# BATTERY_GESTION.net
KiCad netlist of a schematic drawn in Altium Designer
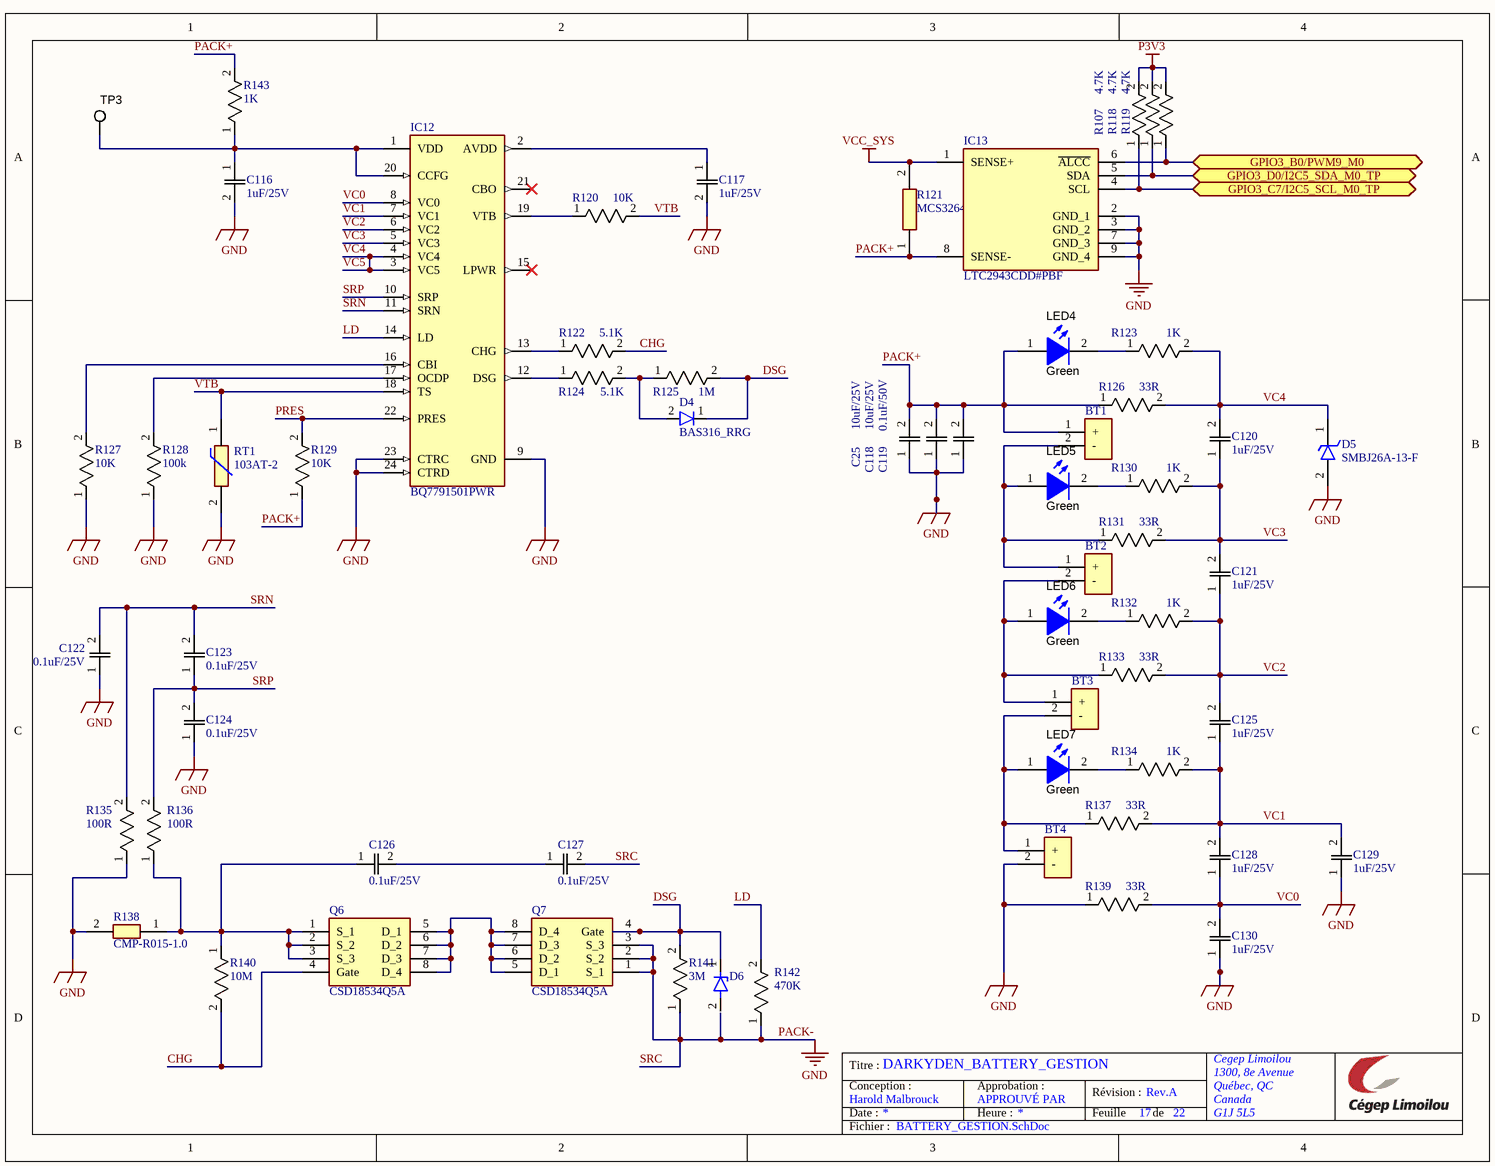
[diagram p0: BATTERY_GESTION.SchDoc]

(export (version "E")
  (design (tool "Eeschema 10.0.6"))
  (components
    (comp (ref "BT1")
      (value "0530480210")
      (footprint "SamacSys:SHDRRA2W35P0X125_1X2_425X550X350P")
      (description "Connector")
      (libsource (lib "SamacSys") (part "Header 1.25MM"))
    )
    (comp (ref "BT2")
      (value "0530480210")
      (footprint "SamacSys:SHDRRA2W35P0X125_1X2_425X550X350P")
      (description "Connector")
      (libsource (lib "SamacSys") (part "Header 1.25MM"))
    )
    (comp (ref "BT3")
      (value "0530480210")
      (footprint "SamacSys:SHDRRA2W35P0X125_1X2_425X550X350P")
      (description "Connector")
      (libsource (lib "SamacSys") (part "Header 1.25MM"))
    )
    (comp (ref "BT4")
      (value "0530480210")
      (footprint "SamacSys:SHDRRA2W35P0X125_1X2_425X550X350P")
      (description "Connector")
      (libsource (lib "SamacSys") (part "Header 1.25MM"))
    )
    (comp (ref "C25")
      (value "10uF/25V")
      (footprint "CAPC220145_88N_KEM")
      (description "10uF / 25 VDC, +85degC, X5R Dielec, +/-10% ¦ KEMET C0805C106K3PACTU 0805")
      (fields
        (field (name "MANUFACTURER") "KEMET")
        (field (name "MANUFACTURER PART NUMBER") "C0805C106K3PACTU")
      )
      (libsource (lib "C0805C106K3PACTU") (part "C0805C106K3PACTU"))
    )
    (comp (ref "C116")
      (value "1uF/25V")
      (footprint "SamacSys:C0805")
      (description "1 µF, 25 V (DC), ±10 %, SMD 0805, X7R, C0805C105K3RAC7800")
      (fields
        (field (name "MANUFACTURER_PART_NUMBER") "C0805C105K3RACTU")
        (field (name "MOUSER PART NUMBER") "80-C0805C105K3R")
      )
      (libsource (lib "SamacSys") (part "C0805C105K3RACTU"))
    )
    (comp (ref "C117")
      (value "1uF/25V")
      (footprint "SamacSys:C0805")
      (description "1 µF, 25 V (DC), ±10 %, SMD 0805, X7R, C0805C105K3RAC7800")
      (fields
        (field (name "MANUFACTURER_PART_NUMBER") "C0805C105K3RACTU")
        (field (name "MOUSER PART NUMBER") "80-C0805C105K3R")
      )
      (libsource (lib "SamacSys") (part "C0805C105K3RACTU"))
    )
    (comp (ref "C118")
      (value "10uF/25V")
      (footprint "CAPC220145_88N_KEM")
      (description "10uF / 25 VDC, +85degC, X5R Dielec, +/-10% ¦ KEMET C0805C106K3PACTU 0805")
      (fields
        (field (name "MANUFACTURER") "KEMET")
        (field (name "MANUFACTURER PART NUMBER") "C0805C106K3PACTU")
      )
      (libsource (lib "C0805C106K3PACTU") (part "C0805C106K3PACTU"))
    )
    (comp (ref "C119")
      (value "0.1uF/50V")
      (footprint "SamacSys:C0805")
      (description "0.1uF/50V X7R 10% 0805 Multilayer Ceramic Capacitors Mlcc Smd/Smt Rohs")
      (fields
        (field (name "MANUFACTURER_PART_NUMBER") "C0805C104K5RACTU")
        (field (name "MOUSER PART NUMBER") "80-C0805C104K5R")
      )
      (libsource (lib "SamacSys") (part "C0805C104K5RACTU"))
    )
    (comp (ref "C120")
      (value "1uF/25V")
      (footprint "SamacSys:C0805")
      (description "1 µF, 25 V (DC), ±10 %, SMD 0805, X7R, C0805C105K3RAC7800")
      (fields
        (field (name "MANUFACTURER_PART_NUMBER") "C0805C105K3RACTU")
        (field (name "MOUSER PART NUMBER") "80-C0805C105K3R")
      )
      (libsource (lib "SamacSys") (part "C0805C105K3RACTU"))
    )
    (comp (ref "C121")
      (value "1uF/25V")
      (footprint "SamacSys:C0805")
      (description "1 µF, 25 V (DC), ±10 %, SMD 0805, X7R, C0805C105K3RAC7800")
      (fields
        (field (name "MANUFACTURER_PART_NUMBER") "C0805C105K3RACTU")
        (field (name "MOUSER PART NUMBER") "80-C0805C105K3R")
      )
      (libsource (lib "SamacSys") (part "C0805C105K3RACTU"))
    )
    (comp (ref "C122")
      (value "0.1uF/25V")
      (footprint "CAPC220145_88N_KEM")
      (description "0.1uF 25V X7R 10% SMD 0805 125C Plastic T/R")
      (fields
        (field (name "MANUFACTURER") "KEMET")
        (field (name "MANUFACTURER PART NUMBER") "C0805C104K3RACTU")
      )
      (libsource (lib "C0805C104K3RACTU") (part "C0805C104K3RACTU"))
    )
    (comp (ref "C123")
      (value "0.1uF/25V")
      (footprint "CAPC220145_88N_KEM")
      (description "0.1uF 25V X7R 10% SMD 0805 125C Plastic T/R")
      (fields
        (field (name "MANUFACTURER") "KEMET")
        (field (name "MANUFACTURER PART NUMBER") "C0805C104K3RACTU")
      )
      (libsource (lib "C0805C104K3RACTU") (part "C0805C104K3RACTU"))
    )
    (comp (ref "C124")
      (value "0.1uF/25V")
      (footprint "CAPC220145_88N_KEM")
      (description "0.1uF 25V X7R 10% SMD 0805 125C Plastic T/R")
      (fields
        (field (name "MANUFACTURER") "KEMET")
        (field (name "MANUFACTURER PART NUMBER") "C0805C104K3RACTU")
      )
      (libsource (lib "C0805C104K3RACTU") (part "C0805C104K3RACTU"))
    )
    (comp (ref "C125")
      (value "1uF/25V")
      (footprint "SamacSys:C0805")
      (description "1 µF, 25 V (DC), ±10 %, SMD 0805, X7R, C0805C105K3RAC7800")
      (fields
        (field (name "MANUFACTURER_PART_NUMBER") "C0805C105K3RACTU")
        (field (name "MOUSER PART NUMBER") "80-C0805C105K3R")
      )
      (libsource (lib "SamacSys") (part "C0805C105K3RACTU"))
    )
    (comp (ref "C126")
      (value "0.1uF/25V")
      (footprint "CAPC220145_88N_KEM")
      (description "0.1uF 25V X7R 10% SMD 0805 125C Plastic T/R")
      (fields
        (field (name "MANUFACTURER") "KEMET")
        (field (name "MANUFACTURER PART NUMBER") "C0805C104K3RACTU")
      )
      (libsource (lib "C0805C104K3RACTU") (part "C0805C104K3RACTU"))
    )
    (comp (ref "C127")
      (value "0.1uF/25V")
      (footprint "CAPC220145_88N_KEM")
      (description "0.1uF 25V X7R 10% SMD 0805 125C Plastic T/R")
      (fields
        (field (name "MANUFACTURER") "KEMET")
        (field (name "MANUFACTURER PART NUMBER") "C0805C104K3RACTU")
      )
      (libsource (lib "C0805C104K3RACTU") (part "C0805C104K3RACTU"))
    )
    (comp (ref "C128")
      (value "1uF/25V")
      (footprint "SamacSys:C0805")
      (description "1 µF, 25 V (DC), ±10 %, SMD 0805, X7R, C0805C105K3RAC7800")
      (fields
        (field (name "MANUFACTURER_PART_NUMBER") "C0805C105K3RACTU")
        (field (name "MOUSER PART NUMBER") "80-C0805C105K3R")
      )
      (libsource (lib "SamacSys") (part "C0805C105K3RACTU"))
    )
    (comp (ref "C129")
      (value "1uF/25V")
      (footprint "SamacSys:C0805")
      (description "1 µF, 25 V (DC), ±10 %, SMD 0805, X7R, C0805C105K3RAC7800")
      (fields
        (field (name "MANUFACTURER_PART_NUMBER") "C0805C105K3RACTU")
        (field (name "MOUSER PART NUMBER") "80-C0805C105K3R")
      )
      (libsource (lib "SamacSys") (part "C0805C105K3RACTU"))
    )
    (comp (ref "C130")
      (value "1uF/25V")
      (footprint "SamacSys:C0805")
      (description "1 µF, 25 V (DC), ±10 %, SMD 0805, X7R, C0805C105K3RAC7800")
      (fields
        (field (name "MANUFACTURER_PART_NUMBER") "C0805C105K3RACTU")
        (field (name "MOUSER PART NUMBER") "80-C0805C105K3R")
      )
      (libsource (lib "SamacSys") (part "C0805C105K3RACTU"))
    )
    (comp (ref "D4")
      (value "BAS316_RRG")
      (footprint "SamacSys:BAS316RRG")
      (description "Rectifier Diode Small Signal Switching 0.25A 4ns 2-Pin SOD-323 T/R")
      (fields
        (field (name "MANUFACTURER_PART_NUMBER") "BAS316 RRG")
        (field (name "MOUSER PART NUMBER") "821-BAS316RRG")
      )
      (libsource (lib "SamacSys") (part "BAS316_RRG"))
    )
    (comp (ref "D5")
      (value "SMBJ26A-13-F")
      (footprint "SamacSys:DIOM5336X250N")
      (description "TVS DIODE 26VWM 42.1VC SMB")
      (fields (field (name "MOUSER PART NUMBER") "621-SMBJ26A-13-F"))
      (libsource (lib "SamacSys") (part "SMBJ26A-13-F"))
    )
    (comp (ref "D6")
      (value "MMSZ5248B-7-F")
      (footprint "SamacSys:SOD3716X115N")
      (description "Zener Diode 18 V 500 mW ±5% Surface Mount SOD-123")
      (libsource (lib "SamacSys") (part "MMSZ5248B-7-F"))
    )
    (comp (ref "IC12")
      (value "BQ7791501PWR")
      (footprint "SamacSys:SOP65P640X120-24N")
      (description "/Polymer 3~5 TSSOP-24 Battery Management ICs ROHS")
      (fields
        (field (name "MOUSER PART NUMBER") "595-BQ7791501PWR")
        (field (name "MANUFACTURER") "Texas Instruments")
      )
      (libsource (lib "SamacSys") (part "BQ7791501PWR"))
    )
    (comp (ref "IC13")
      (value "LTC2943CDD#PBF")
      (footprint "SamacSys:SON50P300X300X80-9N-D")
      (description "LTC2943 - Multicell Battery Gas Gauge with Temperature, Voltage and Current Measurement")
      (fields
        (field (name "MOUSER PART NUMBER") "584-LTC2943CDD#PBF")
        (field (name "MANUFACTURER") "Analog Devices / Linear Technology")
      )
      (libsource (lib "SamacSys") (part "LTC2943CDD#PBF"))
    )
    (comp (ref "LED4")
      (value "Green")
      (footprint "LED_LTST-C190")
      (description "LED, Green, SMD")
      (fields (field (name "MANUFACTURER") "Lite-On") (field (name "PARTNUMBER") "LTST-C190GKT"))
      (libsource (lib "texas_instrument_power") (part "LED_Gr_SMD"))
    )
    (comp (ref "LED5")
      (value "Green")
      (footprint "LED_LTST-C190")
      (description "LED, Green, SMD")
      (fields (field (name "MANUFACTURER") "Lite-On") (field (name "PARTNUMBER") "LTST-C190GKT"))
      (libsource (lib "texas_instrument_power") (part "LED_Gr_SMD"))
    )
    (comp (ref "LED6")
      (value "Green")
      (footprint "LED_LTST-C190")
      (description "LED, Green, SMD")
      (fields (field (name "MANUFACTURER") "Lite-On") (field (name "PARTNUMBER") "LTST-C190GKT"))
      (libsource (lib "texas_instrument_power") (part "LED_Gr_SMD"))
    )
    (comp (ref "LED7")
      (value "Green")
      (footprint "LED_LTST-C190")
      (description "LED, Green, SMD")
      (fields (field (name "MANUFACTURER") "Lite-On") (field (name "PARTNUMBER") "LTST-C190GKT"))
      (libsource (lib "texas_instrument_power") (part "LED_Gr_SMD"))
    )
    (comp (ref "Q6")
      (value "CSD18534Q5A")
      (footprint "SamacSys:Q5A")
      (description "MOSFET N-Channel 60 V 13A (Ta), 50A (Tc) 3.1W (Ta), 77W (Tc) Surface Mount 8-VSONP (5x6)")
      (fields (field (name "MOUSER PART NUMBER") "595-CSD18534Q5A"))
      (libsource (lib "") (part "CSD18534Q5A_1"))
    )
    (comp (ref "Q7")
      (value "CSD18534Q5A")
      (footprint "SamacSys:Q5A")
      (description "MOSFET N-Channel 60 V 13A (Ta), 50A (Tc) 3.1W (Ta), 77W (Tc) Surface Mount 8-VSONP (5x6)")
      (fields (field (name "MOUSER PART NUMBER") "595-CSD18534Q5A"))
      (libsource (lib "SamacSys") (part "CSD18534Q5A"))
    )
    (comp (ref "R107")
      (value "4.7K")
      (footprint "RC0603N_PAN")
      (description "Res Thin Film 0603 4.7K Ohm 0.1% 0.1W ±25ppm/°C Molded SMD Punched Carrier T/R")
      (fields
        (field (name "MANUFACTURER") "Panasonic")
        (field (name "MANUFACTURER PART NUMBER") "ERA-3AEB472V")
      )
      (libsource (lib "ERA-3AEB472V") (part "ERA-3AEB472V"))
    )
    (comp (ref "R118")
      (value "4.7K")
      (footprint "RC0603N_PAN")
      (description "Res Thin Film 0603 4.7K Ohm 0.1% 0.1W ±25ppm/°C Molded SMD Punched Carrier T/R")
      (fields
        (field (name "MANUFACTURER") "Panasonic")
        (field (name "MANUFACTURER PART NUMBER") "ERA-3AEB472V")
      )
      (libsource (lib "ERA-3AEB472V") (part "ERA-3AEB472V"))
    )
    (comp (ref "R119")
      (value "4.7K")
      (footprint "RC0603N_PAN")
      (description "Res Thin Film 0603 4.7K Ohm 0.1% 0.1W ±25ppm/°C Molded SMD Punched Carrier T/R")
      (fields
        (field (name "MANUFACTURER") "Panasonic")
        (field (name "MANUFACTURER PART NUMBER") "ERA-3AEB472V")
      )
      (libsource (lib "ERA-3AEB472V") (part "ERA-3AEB472V"))
    )
    (comp (ref "R120")
      (value "10K")
      (footprint "SamacSys:ERJ3EKF1000V")
      (description "10K Ohm 5% Res Thick Film 0603  0.1W(1/10W) ±200ppm/C Pad SMD Automotive T/R")
      (fields
        (field (name "MANUFACTURER_PART_NUMBER") "ERJ-3GEYJ103V")
        (field (name "MOUSER PART NUMBER") "667-ERJ-3GEYJ103V")
      )
      (libsource (lib "SamacSys") (part "ERJ-3GEYJ103V"))
    )
    (comp (ref "R121")
      (value "MCS3264R010FER")
      (footprint "SamacSys:RESC6432X62N")
      (description "Res Metal Alloy 2512 0.01 Ohm 1% 2W 50ppm/ C Molded SMD T/R")
      (fields (field (name "MOUSER PART NUMBER") "588-MCS3264R010FER") (field (name "MANUFACTURER") "Ohmite"))
      (libsource (lib "SamacSys") (part "MCS3264R010FER"))
    )
    (comp (ref "R122")
      (value "5.1K")
      (footprint "SamacSys:ERA3AEB101V")
      (description "5.1K Ohm 0.05% 0.1W ±10ppm/°C Molded Res Thin Film 0603 SMD Punched Carrier T/R")
      (fields
        (field (name "MANUFACTURER_PART_NUMBER") "ERA-3ARW512V")
        (field (name "MOUSER PART NUMBER") "667-ERA-3ARW512V")
      )
      (libsource (lib "SamacSys") (part "ERA-3ARW512V"))
    )
    (comp (ref "R123")
      (value "1K")
      (footprint "SamacSys:RESC1608X55N")
      (description "1K Ohm 1% 1/10W Res Thick Film 0603 ±100ppm/°C Molded SMD Punched Carrier T/R")
      (fields
        (field (name "MANUFACTURER_PART_NUMBER") "ERJ-3EKF1001V")
        (field (name "MOUSER PART NUMBER") "667-ERJ-3EKF1001V")
      )
      (libsource (lib "SamacSys") (part "ERJ-3EKF1001V"))
    )
    (comp (ref "R124")
      (value "5.1K")
      (footprint "SamacSys:ERA3AEB101V")
      (description "5.1K Ohm 0.05% 0.1W ±10ppm/°C Molded Res Thin Film 0603 SMD Punched Carrier T/R")
      (fields
        (field (name "MANUFACTURER_PART_NUMBER") "ERA-3ARW512V")
        (field (name "MOUSER PART NUMBER") "667-ERA-3ARW512V")
      )
      (libsource (lib "SamacSys") (part "ERA-3ARW512V"))
    )
    (comp (ref "R125")
      (value "1M")
      (footprint "SamacSys:ERJ3EKF1000V")
      (description "1M Ohm Res Thick Film 0603 5% 0.1W(1/10W) +/-200ppm/ßC SMD Automotive T/R")
      (fields
        (field (name "MANUFACTURER_PART_NUMBER") "ERJ-3GEYJ105V")
        (field (name "MOUSER PART NUMBER") "667-ERJ-3GEYJ105V")
      )
      (libsource (lib "SamacSys") (part "ERJ-3GEYJ105V"))
    )
    (comp (ref "R126")
      (value "33R")
      (footprint "RC0603N_PAN")
      (description "Res Thick Film 0603 33 Ohm 1% 0.1W ±100ppm/°C Molded SMD Punched Carrier T/R")
      (fields
        (field (name "MANUFACTURER") "Panasonic")
        (field (name "MANUFACTURER PART NUMBER") "ERJ-3EKF33R0V")
      )
      (libsource (lib "ERJ-3EKF33R0V") (part "ERJ-3EKF33R0V"))
    )
    (comp (ref "R127")
      (value "10K")
      (footprint "SamacSys:ERJ3EKF1000V")
      (description "10K Ohm 5% Res Thick Film 0603  0.1W(1/10W) ±200ppm/C Pad SMD Automotive T/R")
      (fields
        (field (name "MANUFACTURER_PART_NUMBER") "ERJ-3GEYJ103V")
        (field (name "MOUSER PART NUMBER") "667-ERJ-3GEYJ103V")
      )
      (libsource (lib "SamacSys") (part "ERJ-3GEYJ103V"))
    )
    (comp (ref "R128")
      (value "100k")
      (footprint "SamacSys:ERJ3EKF1000V")
      (description "100K Ohm 5%  Res Thick Film 0603 1/10W +/-200ppm/ßC Molded SMD Punched Carrier T/R")
      (fields
        (field (name "MANUFACTURER_PART_NUMBER") "ERJ-3GEYJ104V")
        (field (name "MOUSER PART NUMBER") "667-ERJ-3GEYJ104V")
      )
      (libsource (lib "SamacSys") (part "ERJ-3GEYJ104V"))
    )
    (comp (ref "R129")
      (value "10K")
      (footprint "SamacSys:ERJ3EKF1000V")
      (description "10K Ohm 5% Res Thick Film 0603  0.1W(1/10W) ±200ppm/C Pad SMD Automotive T/R")
      (fields
        (field (name "MANUFACTURER_PART_NUMBER") "ERJ-3GEYJ103V")
        (field (name "MOUSER PART NUMBER") "667-ERJ-3GEYJ103V")
      )
      (libsource (lib "SamacSys") (part "ERJ-3GEYJ103V"))
    )
    (comp (ref "R130")
      (value "1K")
      (footprint "SamacSys:RESC1608X55N")
      (description "1K Ohm 1% 1/10W Res Thick Film 0603 ±100ppm/°C Molded SMD Punched Carrier T/R")
      (fields
        (field (name "MANUFACTURER_PART_NUMBER") "ERJ-3EKF1001V")
        (field (name "MOUSER PART NUMBER") "667-ERJ-3EKF1001V")
      )
      (libsource (lib "SamacSys") (part "ERJ-3EKF1001V"))
    )
    (comp (ref "R131")
      (value "33R")
      (footprint "RC0603N_PAN")
      (description "Res Thick Film 0603 33 Ohm 1% 0.1W ±100ppm/°C Molded SMD Punched Carrier T/R")
      (fields
        (field (name "MANUFACTURER") "Panasonic")
        (field (name "MANUFACTURER PART NUMBER") "ERJ-3EKF33R0V")
      )
      (libsource (lib "ERJ-3EKF33R0V") (part "ERJ-3EKF33R0V"))
    )
    (comp (ref "R132")
      (value "1K")
      (footprint "SamacSys:RESC1608X55N")
      (description "1K Ohm 1% 1/10W Res Thick Film 0603 ±100ppm/°C Molded SMD Punched Carrier T/R")
      (fields
        (field (name "MANUFACTURER_PART_NUMBER") "ERJ-3EKF1001V")
        (field (name "MOUSER PART NUMBER") "667-ERJ-3EKF1001V")
      )
      (libsource (lib "SamacSys") (part "ERJ-3EKF1001V"))
    )
    (comp (ref "R133")
      (value "33R")
      (footprint "RC0603N_PAN")
      (description "Res Thick Film 0603 33 Ohm 1% 0.1W ±100ppm/°C Molded SMD Punched Carrier T/R")
      (fields
        (field (name "MANUFACTURER") "Panasonic")
        (field (name "MANUFACTURER PART NUMBER") "ERJ-3EKF33R0V")
      )
      (libsource (lib "ERJ-3EKF33R0V") (part "ERJ-3EKF33R0V"))
    )
    (comp (ref "R134")
      (value "1K")
      (footprint "SamacSys:RESC1608X55N")
      (description "1K Ohm 1% 1/10W Res Thick Film 0603 ±100ppm/°C Molded SMD Punched Carrier T/R")
      (fields
        (field (name "MANUFACTURER_PART_NUMBER") "ERJ-3EKF1001V")
        (field (name "MOUSER PART NUMBER") "667-ERJ-3EKF1001V")
      )
      (libsource (lib "SamacSys") (part "ERJ-3EKF1001V"))
    )
    (comp (ref "R135")
      (value "100R")
      (footprint "SamacSys:RESC1608X55N")
      (description "100 Ohm 1% 1/10W 0603 ±100ppm/°C Molded SMD Punched Carrier T/R")
      (fields
        (field (name "MANUFACTURER_PART_NUMBER") "ERJ-3EKF1000V")
        (field (name "MOUSER PART NUMBER") "667-ERJ-3EKF1000V")
      )
      (libsource (lib "SamacSys") (part "ERJ-3EKF1000V"))
    )
    (comp (ref "R136")
      (value "100R")
      (footprint "SamacSys:RESC1608X55N")
      (description "100 Ohm 1% 1/10W 0603 ±100ppm/°C Molded SMD Punched Carrier T/R")
      (fields
        (field (name "MANUFACTURER_PART_NUMBER") "ERJ-3EKF1000V")
        (field (name "MOUSER PART NUMBER") "667-ERJ-3EKF1000V")
      )
      (libsource (lib "SamacSys") (part "ERJ-3EKF1000V"))
    )
    (comp (ref "R137")
      (value "33R")
      (footprint "RC0603N_PAN")
      (description "Res Thick Film 0603 33 Ohm 1% 0.1W ±100ppm/°C Molded SMD Punched Carrier T/R")
      (fields
        (field (name "MANUFACTURER") "Panasonic")
        (field (name "MANUFACTURER PART NUMBER") "ERJ-3EKF33R0V")
      )
      (libsource (lib "ERJ-3EKF33R0V") (part "ERJ-3EKF33R0V"))
    )
    (comp (ref "R138")
      (value "CMP-R015-1.0")
      (footprint "SamacSys:RESC5025X70N")
      (description "Package 2010")
      (fields
        (field (name "MANUFACTURER_PART_NUMBER") "CRCW20100000Z0EFHP")
        (field (name "MOUSER PART NUMBER") "71-CRCW20100000Z0EFH")
      )
      (libsource (lib "SamacSys") (part "Resistor 2010"))
    )
    (comp (ref "R139")
      (value "33R")
      (footprint "RC0603N_PAN")
      (description "Res Thick Film 0603 33 Ohm 1% 0.1W ±100ppm/°C Molded SMD Punched Carrier T/R")
      (fields
        (field (name "MANUFACTURER") "Panasonic")
        (field (name "MANUFACTURER PART NUMBER") "ERJ-3EKF33R0V")
      )
      (libsource (lib "ERJ-3EKF33R0V") (part "ERJ-3EKF33R0V"))
    )
    (comp (ref "R140")
      (value "10M")
      (footprint "SamacSys:ERJS03J155V")
      (description "10Mohm 5%  SMD 0603   Anti-Sulfur AEC-Q200")
      (fields
        (field (name "MANUFACTURER_PART_NUMBER") "ERJ-U03J106V")
        (field (name "MOUSER PART NUMBER") "667-ERJ-U03J106V")
      )
      (libsource (lib "SamacSys") (part "ERJ-U03J106V"))
    )
    (comp (ref "R141")
      (value "3M")
      (footprint "SamacSys:ERJ3EKF1000V")
      (description "3M Ohm 5% 1/10W Res Thick Film 0603 -400ppm/ to 150p¦")
      (fields
        (field (name "MANUFACTURER_PART_NUMBER") "ERJ-3GEYJ305V")
        (field (name "MOUSER PART NUMBER") "667-ERJ-3GEYJ305V")
      )
      (libsource (lib "SamacSys") (part "ERJ-3GEYJ305V"))
    )
    (comp (ref "R142")
      (value "470K")
      (footprint "SamacSys:RESC1608X55N")
      (description "470K Ohm 1% 0.1W  Res Thick Film 0603 ±100ppm/°C Molded SMD Punched Carrier T/R")
      (fields
        (field (name "MANUFACTURER_PART_NUMBER") "ERJ-3EKF4703V")
        (field (name "MOUSER PART NUMBER") "667-ERJ-3EKF4703V")
      )
      (libsource (lib "SamacSys") (part "ERJ-3EKF4703V"))
    )
    (comp (ref "R143")
      (value "1K")
      (footprint "SamacSys:RESC1608X55N")
      (description "1K Ohm 1% 1/10W Res Thick Film 0603 ±100ppm/°C Molded SMD Punched Carrier T/R")
      (fields
        (field (name "MANUFACTURER_PART_NUMBER") "ERJ-3EKF1001V")
        (field (name "MOUSER PART NUMBER") "667-ERJ-3EKF1001V")
      )
      (libsource (lib "SamacSys") (part "ERJ-3EKF1001V"))
    )
    (comp (ref "RT1")
      (value "103AT-2")
      (footprint "SamacSys:103AT2")
      (description "NTC Thermistor 10k Bead")
      (fields (field (name "MOUSER PART NUMBER") "954-103AT-2"))
      (libsource (lib "SamacSys") (part "103AT-2"))
    )
    (comp (ref "TP3")
      (value "5016")
      (footprint "Testpoint_Keystone_Compact")
      (description "Test Point, Compact, SMT")
      (fields (field (name "MANUFACTURER") "Keystone") (field (name "PUBLISHER") "Texas Instruments"))
      (libsource (lib "texas_instrument_power") (part "TEST_POINT1"))
    )
  )
  (nets
    (net (code "1") (name "/CHG") (class "Default")
      (node (ref "Q6") (pin "4") (pinfunction "Gate_4") (pintype "passive"))
      (node (ref "R122") (pin "2") (pinfunction "2_2") (pintype "passive"))
      (node (ref "R140") (pin "2") (pinfunction "2_2") (pintype "passive"))
    )
    (net (code "2") (name "/DSG") (class "Default")
      (node (ref "D4") (pin "1") (pinfunction "K_1") (pintype "passive"))
      (node (ref "D6") (pin "1") (pinfunction "K_1") (pintype "passive"))
      (node (ref "Q7") (pin "4") (pinfunction "Gate_4") (pintype "passive"))
      (node (ref "R125") (pin "2") (pinfunction "2_2") (pintype "passive"))
      (node (ref "R141") (pin "2") (pinfunction "2_2") (pintype "passive"))
    )
    (net (code "3") (name "/GPIO3_B0{slash}PWM9_M0") (class "Default")
      (node (ref "IC13") (pin "6") (pinfunction "~{ALCC}_6") (pintype "passive"))
      (node (ref "R119") (pin "1") (pinfunction "1_1") (pintype "passive"))
    )
    (net (code "4") (name "/GPIO3_C7{slash}I2C5_SCL_M0_TP") (class "Default")
      (node (ref "IC13") (pin "4") (pinfunction "SCL_4") (pintype "passive"))
      (node (ref "R107") (pin "1") (pinfunction "1_1") (pintype "passive"))
    )
    (net (code "5") (name "/GPIO3_D0{slash}I2C5_SDA_M0_TP") (class "Default")
      (node (ref "IC13") (pin "5") (pinfunction "SDA_5") (pintype "passive"))
      (node (ref "R118") (pin "1") (pinfunction "1_1") (pintype "passive"))
    )
    (net (code "6") (name "/LD") (class "Default")
      (node (ref "IC12") (pin "14") (pinfunction "LD_14") (pintype "input"))
      (node (ref "R142") (pin "2") (pinfunction "2_2") (pintype "passive"))
    )
    (net (code "7") (name "/PACK+") (class "Default")
      (node (ref "BT1") (pin "1") (pinfunction "+_1") (pintype "passive"))
      (node (ref "C118") (pin "2") (pinfunction "2_2") (pintype "passive"))
      (node (ref "C119") (pin "2") (pinfunction "2_2") (pintype "passive"))
      (node (ref "C25") (pin "2") (pinfunction "2_2") (pintype "passive"))
      (node (ref "IC13") (pin "8") (pinfunction "SENSE-_8") (pintype "passive"))
      (node (ref "LED4") (pin "1") (pinfunction "A_1") (pintype "passive"))
      (node (ref "R121") (pin "1") (pinfunction "1_1") (pintype "passive"))
      (node (ref "R126") (pin "1") (pinfunction "1_1") (pintype "passive"))
      (node (ref "R129") (pin "1") (pinfunction "1_1") (pintype "passive"))
      (node (ref "R143") (pin "2") (pinfunction "2_2") (pintype "passive"))
    )
    (net (code "8") (name "/PRES") (class "Default")
      (node (ref "IC12") (pin "22") (pinfunction "PRES_22") (pintype "input"))
      (node (ref "R129") (pin "2") (pinfunction "2_2") (pintype "passive"))
    )
    (net (code "9") (name "/SRN") (class "Default")
      (node (ref "C122") (pin "2") (pinfunction "2_2") (pintype "passive"))
      (node (ref "C123") (pin "2") (pinfunction "2_2") (pintype "passive"))
      (node (ref "IC12") (pin "11") (pinfunction "SRN_11") (pintype "input"))
      (node (ref "R135") (pin "2") (pinfunction "2_2") (pintype "passive"))
    )
    (net (code "10") (name "/SRP") (class "Default")
      (node (ref "C123") (pin "1") (pinfunction "1_1") (pintype "passive"))
      (node (ref "C124") (pin "2") (pinfunction "2_2") (pintype "passive"))
      (node (ref "IC12") (pin "10") (pinfunction "SRP_10") (pintype "input"))
      (node (ref "R136") (pin "2") (pinfunction "2_2") (pintype "passive"))
    )
    (net (code "11") (name "/VC0") (class "Default")
      (node (ref "C128") (pin "1") (pinfunction "1_1") (pintype "passive"))
      (node (ref "C130") (pin "2") (pinfunction "2_2") (pintype "passive"))
      (node (ref "IC12") (pin "8") (pinfunction "VC0_8") (pintype "input"))
      (node (ref "R139") (pin "2") (pinfunction "2_2") (pintype "passive"))
    )
    (net (code "12") (name "/VC1") (class "Default")
      (node (ref "C125") (pin "1") (pinfunction "1_1") (pintype "passive"))
      (node (ref "C128") (pin "2") (pinfunction "2_2") (pintype "passive"))
      (node (ref "C129") (pin "2") (pinfunction "2_2") (pintype "passive"))
      (node (ref "IC12") (pin "7") (pinfunction "VC1_7") (pintype "input"))
      (node (ref "R134") (pin "2") (pinfunction "2_2") (pintype "passive"))
      (node (ref "R137") (pin "2") (pinfunction "2_2") (pintype "passive"))
    )
    (net (code "13") (name "/VC2") (class "Default")
      (node (ref "C121") (pin "1") (pinfunction "1_1") (pintype "passive"))
      (node (ref "C125") (pin "2") (pinfunction "2_2") (pintype "passive"))
      (node (ref "IC12") (pin "6") (pinfunction "VC2_6") (pintype "input"))
      (node (ref "R132") (pin "2") (pinfunction "2_2") (pintype "passive"))
      (node (ref "R133") (pin "2") (pinfunction "2_2") (pintype "passive"))
    )
    (net (code "14") (name "/VC3") (class "Default")
      (node (ref "C120") (pin "1") (pinfunction "1_1") (pintype "passive"))
      (node (ref "C121") (pin "2") (pinfunction "2_2") (pintype "passive"))
      (node (ref "IC12") (pin "5") (pinfunction "VC3_5") (pintype "input"))
      (node (ref "R130") (pin "2") (pinfunction "2_2") (pintype "passive"))
      (node (ref "R131") (pin "2") (pinfunction "2_2") (pintype "passive"))
    )
    (net (code "15") (name "/VC4") (class "Default")
      (node (ref "C120") (pin "2") (pinfunction "2_2") (pintype "passive"))
      (node (ref "D5") (pin "1") (pinfunction "K_1") (pintype "passive"))
      (node (ref "IC12") (pin "3") (pinfunction "VC5_3") (pintype "input"))
      (node (ref "IC12") (pin "4") (pinfunction "VC4_4") (pintype "input"))
      (node (ref "R123") (pin "2") (pinfunction "2_2") (pintype "passive"))
      (node (ref "R126") (pin "2") (pinfunction "2_2") (pintype "passive"))
    )
    (net (code "16") (name "/VTB") (class "Default")
      (node (ref "IC12") (pin "18") (pinfunction "TS_18") (pintype "input"))
      (node (ref "R120") (pin "2") (pinfunction "2_2") (pintype "passive"))
      (node (ref "RT1") (pin "1") (pinfunction "1_1") (pintype "passive"))
    )
    (net (code "17") (name "GND") (class "Default")
      (node (ref "BT4") (pin "2") (pinfunction "-_2") (pintype "passive"))
      (node (ref "C116") (pin "2") (pinfunction "2_2") (pintype "passive"))
      (node (ref "C117") (pin "2") (pinfunction "2_2") (pintype "passive"))
      (node (ref "C118") (pin "1") (pinfunction "1_1") (pintype "passive"))
      (node (ref "C119") (pin "1") (pinfunction "1_1") (pintype "passive"))
      (node (ref "C122") (pin "1") (pinfunction "1_1") (pintype "passive"))
      (node (ref "C124") (pin "1") (pinfunction "1_1") (pintype "passive"))
      (node (ref "C127") (pin "2") (pinfunction "2_2") (pintype "passive"))
      (node (ref "C129") (pin "1") (pinfunction "1_1") (pintype "passive"))
      (node (ref "C130") (pin "1") (pinfunction "1_1") (pintype "passive"))
      (node (ref "C25") (pin "1") (pinfunction "1_1") (pintype "passive"))
      (node (ref "D5") (pin "2") (pinfunction "A_2") (pintype "passive"))
      (node (ref "IC12") (pin "23") (pinfunction "CTRC_23") (pintype "input"))
      (node (ref "IC12") (pin "24") (pinfunction "CTRD_24") (pintype "input"))
      (node (ref "IC12") (pin "9") (pinfunction "GND_9") (pintype "passive"))
      (node (ref "IC13") (pin "2") (pinfunction "GND_1_2") (pintype "passive"))
      (node (ref "IC13") (pin "3") (pinfunction "GND_2_3") (pintype "passive"))
      (node (ref "IC13") (pin "7") (pinfunction "GND_3_7") (pintype "passive"))
      (node (ref "IC13") (pin "9") (pinfunction "GND_4_9") (pintype "passive"))
      (node (ref "Q7") (pin "1") (pinfunction "S_1_1") (pintype "passive"))
      (node (ref "Q7") (pin "2") (pinfunction "S_2_2") (pintype "passive"))
      (node (ref "Q7") (pin "3") (pinfunction "S_3_3") (pintype "passive"))
      (node (ref "R127") (pin "1") (pinfunction "1_1") (pintype "passive"))
      (node (ref "R128") (pin "1") (pinfunction "1_1") (pintype "passive"))
      (node (ref "R135") (pin "1") (pinfunction "1_1") (pintype "passive"))
      (node (ref "R138") (pin "2") (pinfunction "2_2") (pintype "passive"))
      (node (ref "R139") (pin "1") (pinfunction "1_1") (pintype "passive"))
      (node (ref "R141") (pin "1") (pinfunction "1_1") (pintype "passive"))
      (node (ref "R142") (pin "1") (pinfunction "1_1") (pintype "passive"))
      (node (ref "RT1") (pin "2") (pinfunction "2_2") (pintype "passive"))
    )
    (net (code "18") (name "Net-(BT1--)") (class "Default")
      (node (ref "BT1") (pin "2") (pinfunction "-_2") (pintype "passive"))
      (node (ref "BT2") (pin "1") (pinfunction "+_1") (pintype "passive"))
      (node (ref "LED5") (pin "1") (pinfunction "A_1") (pintype "passive"))
      (node (ref "R131") (pin "1") (pinfunction "1_1") (pintype "passive"))
    )
    (net (code "19") (name "Net-(BT2--)") (class "Default")
      (node (ref "BT2") (pin "2") (pinfunction "-_2") (pintype "passive"))
      (node (ref "BT3") (pin "1") (pinfunction "+_1") (pintype "passive"))
      (node (ref "LED6") (pin "1") (pinfunction "A_1") (pintype "passive"))
      (node (ref "R133") (pin "1") (pinfunction "1_1") (pintype "passive"))
    )
    (net (code "20") (name "Net-(BT3--)") (class "Default")
      (node (ref "BT3") (pin "2") (pinfunction "-_2") (pintype "passive"))
      (node (ref "BT4") (pin "1") (pinfunction "+_1") (pintype "passive"))
      (node (ref "LED7") (pin "1") (pinfunction "A_1") (pintype "passive"))
      (node (ref "R137") (pin "1") (pinfunction "1_1") (pintype "passive"))
    )
    (net (code "21") (name "Net-(C126-Pad2)") (class "Default")
      (node (ref "C126") (pin "2") (pinfunction "2_2") (pintype "passive"))
      (node (ref "C127") (pin "1") (pinfunction "1_1") (pintype "passive"))
    )
    (net (code "22") (name "Net-(D4-A)") (class "Default")
      (node (ref "D4") (pin "2") (pinfunction "A_2") (pintype "passive"))
      (node (ref "R124") (pin "2") (pinfunction "2_2") (pintype "passive"))
      (node (ref "R125") (pin "1") (pinfunction "1_1") (pintype "passive"))
    )
    (net (code "23") (name "Net-(IC12-AVDD)") (class "Default")
      (node (ref "C117") (pin "1") (pinfunction "1_1") (pintype "passive"))
      (node (ref "IC12") (pin "2") (pinfunction "AVDD_2") (pintype "output"))
    )
    (net (code "24") (name "Net-(IC12-CBI)") (class "Default")
      (node (ref "IC12") (pin "16") (pinfunction "CBI_16") (pintype "input"))
      (node (ref "R127") (pin "2") (pinfunction "2_2") (pintype "passive"))
    )
    (net (code "25") (name "Net-(IC12-CCFG)") (class "Default")
      (node (ref "C116") (pin "1") (pinfunction "1_1") (pintype "passive"))
      (node (ref "IC12") (pin "1") (pinfunction "VDD_1") (pintype "power_in"))
      (node (ref "IC12") (pin "20") (pinfunction "CCFG_20") (pintype "input"))
      (node (ref "R143") (pin "1") (pinfunction "1_1") (pintype "passive"))
      (node (ref "TP3") (pin "1") (pintype "passive"))
    )
    (net (code "26") (name "Net-(IC12-CHG)") (class "Default")
      (node (ref "IC12") (pin "13") (pinfunction "CHG_13") (pintype "output"))
      (node (ref "R122") (pin "1") (pinfunction "1_1") (pintype "passive"))
    )
    (net (code "27") (name "Net-(IC12-DSG)") (class "Default")
      (node (ref "IC12") (pin "12") (pinfunction "DSG_12") (pintype "output"))
      (node (ref "R124") (pin "1") (pinfunction "1_1") (pintype "passive"))
    )
    (net (code "28") (name "Net-(IC12-OCDP)") (class "Default")
      (node (ref "IC12") (pin "17") (pinfunction "OCDP_17") (pintype "input"))
      (node (ref "R128") (pin "2") (pinfunction "2_2") (pintype "passive"))
    )
    (net (code "29") (name "Net-(IC12-VTB)") (class "Default")
      (node (ref "IC12") (pin "19") (pinfunction "VTB_19") (pintype "output"))
      (node (ref "R120") (pin "1") (pinfunction "1_1") (pintype "passive"))
    )
    (net (code "30") (name "Net-(LED4-K)") (class "Default")
      (node (ref "LED4") (pin "2") (pinfunction "K_2") (pintype "passive"))
      (node (ref "R123") (pin "1") (pinfunction "1_1") (pintype "passive"))
    )
    (net (code "31") (name "Net-(LED5-K)") (class "Default")
      (node (ref "LED5") (pin "2") (pinfunction "K_2") (pintype "passive"))
      (node (ref "R130") (pin "1") (pinfunction "1_1") (pintype "passive"))
    )
    (net (code "32") (name "Net-(LED6-K)") (class "Default")
      (node (ref "LED6") (pin "2") (pinfunction "K_2") (pintype "passive"))
      (node (ref "R132") (pin "1") (pinfunction "1_1") (pintype "passive"))
    )
    (net (code "33") (name "Net-(LED7-K)") (class "Default")
      (node (ref "LED7") (pin "2") (pinfunction "K_2") (pintype "passive"))
      (node (ref "R134") (pin "1") (pinfunction "1_1") (pintype "passive"))
    )
    (net (code "34") (name "Net-(Q6-D_1)") (class "Default")
      (node (ref "Q6") (pin "5") (pinfunction "D_1_5") (pintype "passive"))
      (node (ref "Q6") (pin "6") (pinfunction "D_2_6") (pintype "passive"))
      (node (ref "Q6") (pin "7") (pinfunction "D_3_7") (pintype "passive"))
      (node (ref "Q6") (pin "8") (pinfunction "D_4_8") (pintype "passive"))
      (node (ref "Q7") (pin "5") (pinfunction "D_1_5") (pintype "passive"))
      (node (ref "Q7") (pin "6") (pinfunction "D_2_6") (pintype "passive"))
      (node (ref "Q7") (pin "7") (pinfunction "D_3_7") (pintype "passive"))
      (node (ref "Q7") (pin "8") (pinfunction "D_4_8") (pintype "passive"))
    )
    (net (code "35") (name "Net-(Q6-S_1)") (class "Default")
      (node (ref "C126") (pin "1") (pinfunction "1_1") (pintype "passive"))
      (node (ref "Q6") (pin "1") (pinfunction "S_1_1") (pintype "passive"))
      (node (ref "Q6") (pin "2") (pinfunction "S_2_2") (pintype "passive"))
      (node (ref "Q6") (pin "3") (pinfunction "S_3_3") (pintype "passive"))
      (node (ref "R136") (pin "1") (pinfunction "1_1") (pintype "passive"))
      (node (ref "R138") (pin "1") (pinfunction "1_1") (pintype "passive"))
      (node (ref "R140") (pin "1") (pinfunction "1_1") (pintype "passive"))
    )
    (net (code "36") (name "P3V3") (class "Default")
      (node (ref "R107") (pin "2") (pinfunction "2_2") (pintype "passive"))
      (node (ref "R118") (pin "2") (pinfunction "2_2") (pintype "passive"))
      (node (ref "R119") (pin "2") (pinfunction "2_2") (pintype "passive"))
    )
    (net (code "37") (name "VCC_SYS") (class "Default")
      (node (ref "IC13") (pin "1") (pinfunction "SENSE+_1") (pintype "passive"))
      (node (ref "R121") (pin "2") (pinfunction "2_2") (pintype "passive"))
    )
    (net (code "38") (name "unconnected-(D6-A-Pad2)") (class "Default")
      (node (ref "D6") (pin "2") (pinfunction "A_2") (pintype "passive"))
    )
    (net (code "39") (name "unconnected-(IC12-CBO-Pad21)") (class "Default")
      (node (ref "IC12") (pin "21") (pinfunction "CBO_21") (pintype "output+no_connect"))
    )
    (net (code "40") (name "unconnected-(IC12-LPWR-Pad15)") (class "Default")
      (node (ref "IC12") (pin "15") (pinfunction "LPWR_15") (pintype "output+no_connect"))
    )
  )
)
